# ESP32-S2_pacman.net
KiCad netlist of a schematic drawn in EAGLE
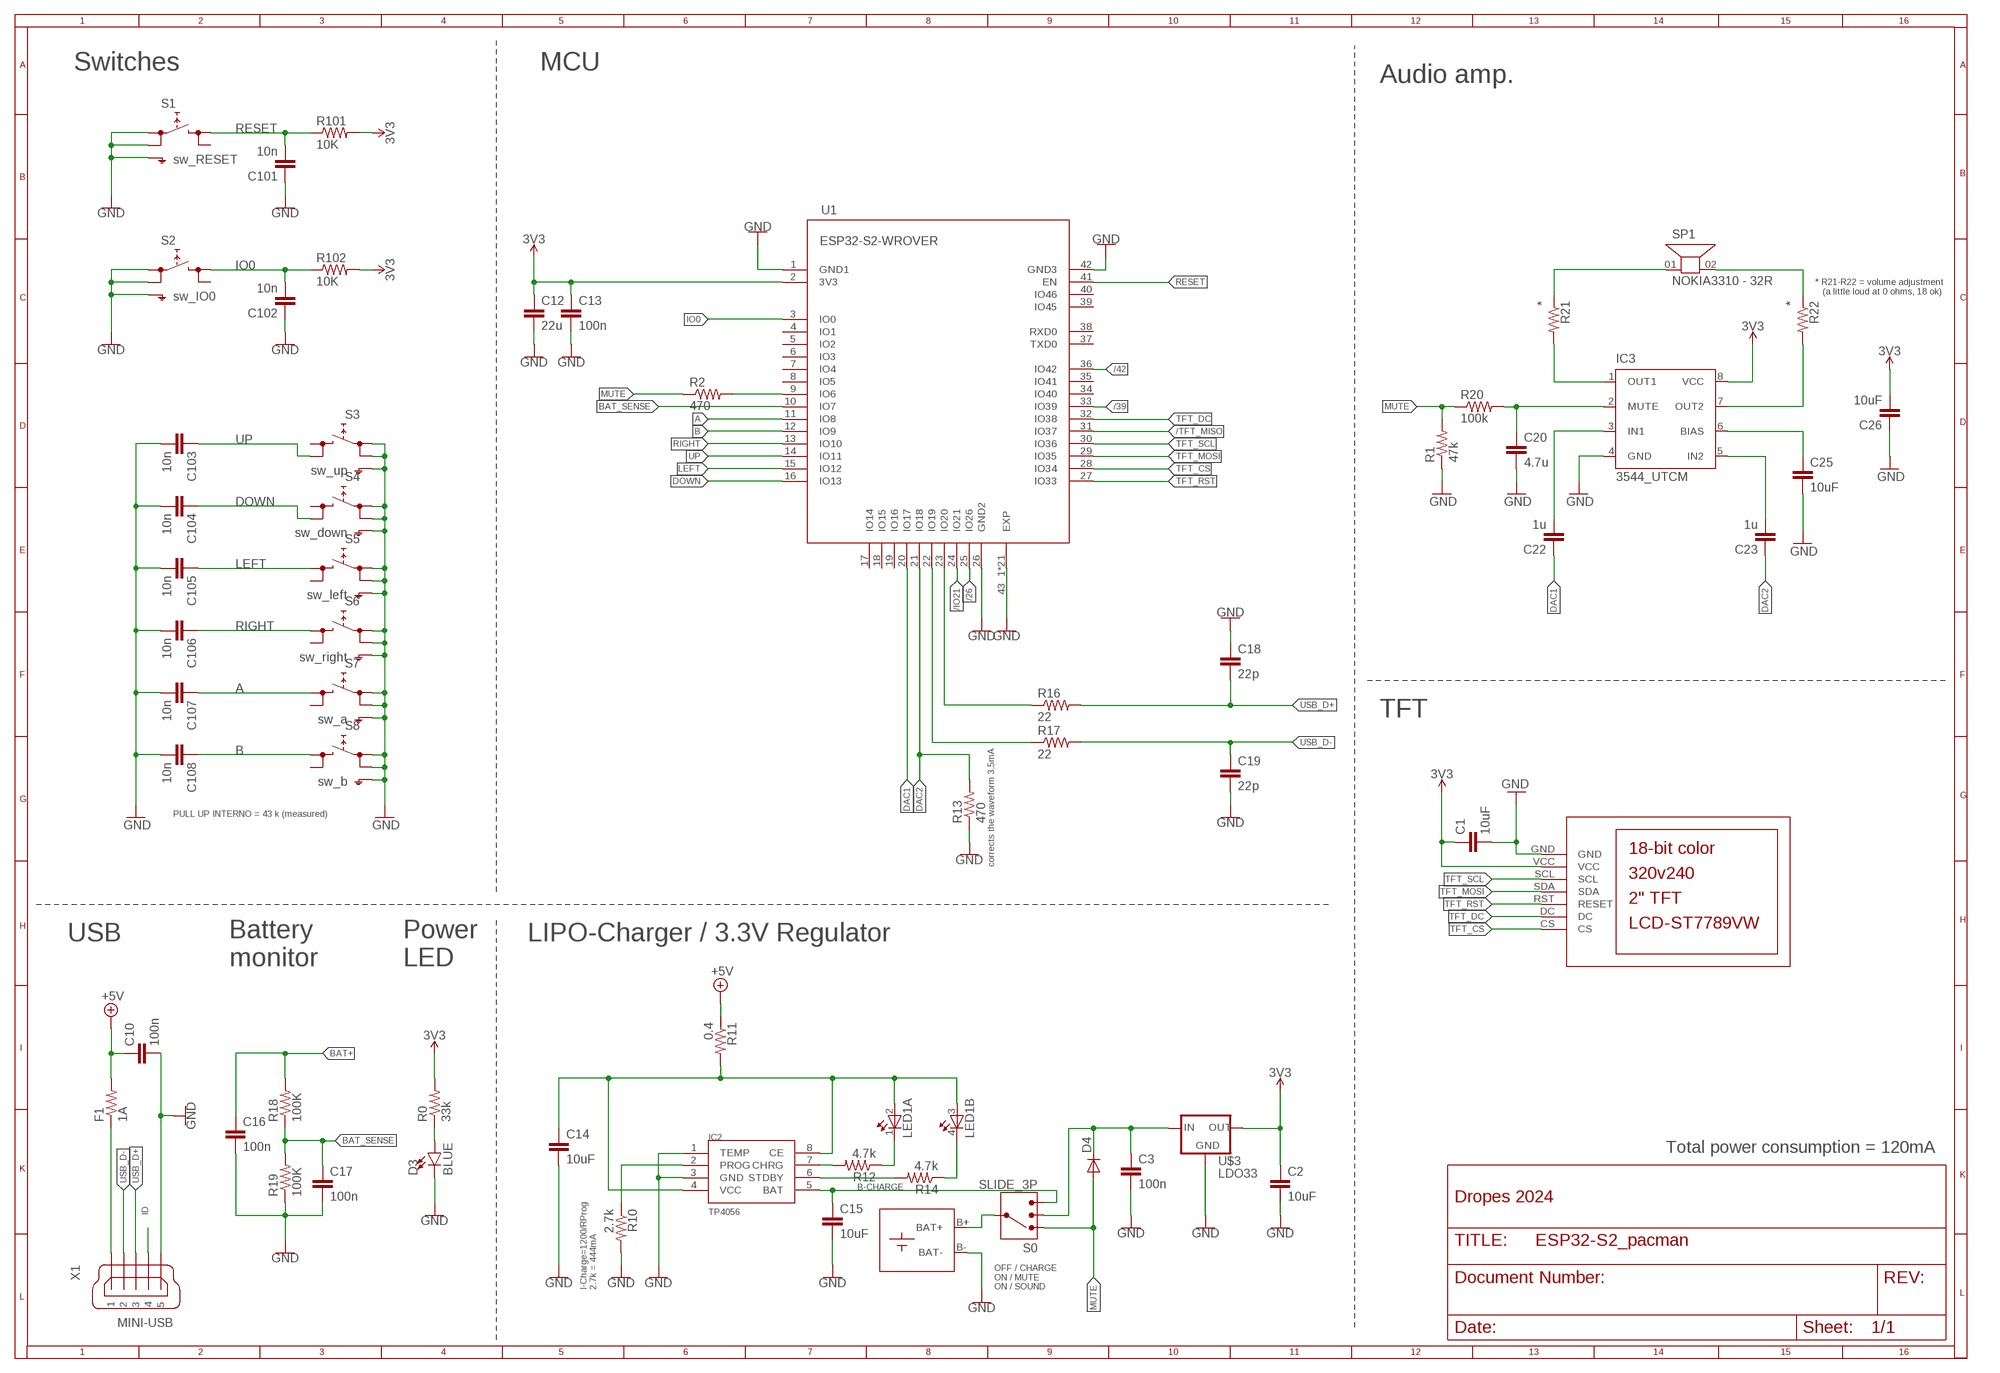
[diagram p0: schematic, sheet 1]

(export (version "E")
  (design (tool "Eeschema 10.0.6"))
  (components
    (comp (ref "C1")
      (value "10uF")
      (footprint "eagle-import:1206")
      (libsource (lib "eagle-import") (part "CAP1206"))
    )
    (comp (ref "C2")
      (value "10uF")
      (footprint "eagle-import:1206")
      (libsource (lib "eagle-import") (part "CAP1206"))
    )
    (comp (ref "C3")
      (value "100n")
      (footprint "eagle-import:0805")
      (libsource (lib "eagle-import") (part "CAP0805"))
    )
    (comp (ref "C10")
      (value "100n")
      (footprint "eagle-import:0805")
      (libsource (lib "eagle-import") (part "CAP0805"))
    )
    (comp (ref "C12")
      (value "22u")
      (footprint "eagle-import:1206")
      (libsource (lib "eagle-import") (part "CAP1206"))
    )
    (comp (ref "C13")
      (value "100n")
      (footprint "eagle-import:0805")
      (libsource (lib "eagle-import") (part "CAP0805"))
    )
    (comp (ref "C14")
      (value "10uF")
      (footprint "eagle-import:1206")
      (libsource (lib "eagle-import") (part "CAP1206"))
    )
    (comp (ref "C15")
      (value "10uF")
      (footprint "eagle-import:1206")
      (libsource (lib "eagle-import") (part "CAP1206"))
    )
    (comp (ref "C16")
      (value "100n")
      (footprint "eagle-import:0805")
      (libsource (lib "eagle-import") (part "CAP0805"))
    )
    (comp (ref "C17")
      (value "100n")
      (footprint "eagle-import:0805")
      (libsource (lib "eagle-import") (part "CAP0805"))
    )
    (comp (ref "C18")
      (value "22p")
      (footprint "eagle-import:0805")
      (libsource (lib "eagle-import") (part "CAP0805"))
    )
    (comp (ref "C19")
      (value "22p")
      (footprint "eagle-import:0805")
      (libsource (lib "eagle-import") (part "CAP0805"))
    )
    (comp (ref "C20")
      (value "4.7u")
      (footprint "eagle-import:0805")
      (libsource (lib "eagle-import") (part "CAP0805"))
    )
    (comp (ref "C22")
      (value "1u")
      (footprint "eagle-import:0805")
      (libsource (lib "eagle-import") (part "CAP0805"))
    )
    (comp (ref "C23")
      (value "1u")
      (footprint "eagle-import:0805")
      (libsource (lib "eagle-import") (part "CAP0805"))
    )
    (comp (ref "C25")
      (value "10uF")
      (footprint "eagle-import:0805")
      (libsource (lib "eagle-import") (part "CAP0805"))
    )
    (comp (ref "C26")
      (value "10uF")
      (footprint "eagle-import:0805")
      (libsource (lib "eagle-import") (part "CAP0805"))
    )
    (comp (ref "C101")
      (value "10n")
      (footprint "eagle-import:0805")
      (libsource (lib "eagle-import") (part "CAP0805"))
    )
    (comp (ref "C102")
      (value "10n")
      (footprint "eagle-import:0805")
      (libsource (lib "eagle-import") (part "CAP0805"))
    )
    (comp (ref "C103")
      (value "10n")
      (footprint "eagle-import:0805")
      (libsource (lib "eagle-import") (part "CAP0805"))
    )
    (comp (ref "C104")
      (value "10n")
      (footprint "eagle-import:0805")
      (libsource (lib "eagle-import") (part "CAP0805"))
    )
    (comp (ref "C105")
      (value "10n")
      (footprint "eagle-import:0805")
      (libsource (lib "eagle-import") (part "CAP0805"))
    )
    (comp (ref "C106")
      (value "10n")
      (footprint "eagle-import:0805")
      (libsource (lib "eagle-import") (part "CAP0805"))
    )
    (comp (ref "C107")
      (value "10n")
      (footprint "eagle-import:0805")
      (libsource (lib "eagle-import") (part "CAP0805"))
    )
    (comp (ref "C108")
      (value "10n")
      (footprint "eagle-import:0805")
      (libsource (lib "eagle-import") (part "CAP0805"))
    )
    (comp (ref "D3")
      (value "BLUE")
      (footprint "eagle-import:LED-1206")
      (libsource (lib "eagle-import") (part "LED-BLUE1206"))
    )
    (comp (ref "D4")
      (value "DIODE-SOD323-W")
      (footprint "eagle-import:SOD323-W")
      (libsource (lib "eagle-import") (part "DIODE-SOD323-W"))
    )
    (comp (ref "F1")
      (value "1A")
      (footprint "eagle-import:0805")
      (libsource (lib "eagle-import") (part "RESISTOR0805-RES"))
    )
    (comp (ref "IC2")
      (value "TP4056")
      (footprint "eagle-import:SOP-8")
      (libsource (lib "eagle-import") (part "TP4056"))
    )
    (comp (ref "IC3")
      (value "3544_UTCM")
      (footprint "eagle-import:SO08")
      (libsource (lib "eagle-import") (part "3544_UTCM"))
    )
    (comp (ref "LED1")
      (value "TOPLED-2--")
      (footprint "eagle-import:P-LCC-4-2")
      (libsource (lib "eagle-import") (part "TOPLED-2--"))
    )
    (comp (ref "R0")
      (value "33k")
      (footprint "eagle-import:0805")
      (libsource (lib "eagle-import") (part "RESISTOR0805-RES"))
    )
    (comp (ref "R1")
      (value "47k")
      (footprint "eagle-import:0805")
      (libsource (lib "eagle-import") (part "RESISTOR0805-RES"))
    )
    (comp (ref "R2")
      (value "470")
      (footprint "eagle-import:0805")
      (libsource (lib "eagle-import") (part "RESISTOR0805-RES"))
    )
    (comp (ref "R10")
      (value "2.7k")
      (footprint "eagle-import:0805")
      (libsource (lib "eagle-import") (part "RESISTOR0805-RES"))
    )
    (comp (ref "R11")
      (value "0.4")
      (footprint "eagle-import:0805")
      (libsource (lib "eagle-import") (part "RESISTOR0805-RES"))
    )
    (comp (ref "R12")
      (value "4.7k")
      (footprint "eagle-import:0805")
      (libsource (lib "eagle-import") (part "RESISTOR0805-RES"))
    )
    (comp (ref "R13")
      (value "470")
      (footprint "eagle-import:0805")
      (libsource (lib "eagle-import") (part "RESISTOR0805-RES"))
    )
    (comp (ref "R14")
      (value "4.7k")
      (footprint "eagle-import:0805")
      (libsource (lib "eagle-import") (part "RESISTOR0805-RES"))
    )
    (comp (ref "R16")
      (value "22")
      (footprint "eagle-import:0805")
      (libsource (lib "eagle-import") (part "RESISTOR0805-RES"))
    )
    (comp (ref "R17")
      (value "22")
      (footprint "eagle-import:0805")
      (libsource (lib "eagle-import") (part "RESISTOR0805-RES"))
    )
    (comp (ref "R18")
      (value "100K")
      (footprint "eagle-import:0805")
      (libsource (lib "eagle-import") (part "RESISTOR0805-RES"))
    )
    (comp (ref "R19")
      (value "100K")
      (footprint "eagle-import:0805")
      (libsource (lib "eagle-import") (part "RESISTOR0805-RES"))
    )
    (comp (ref "R20")
      (value "100k")
      (footprint "eagle-import:0805")
      (libsource (lib "eagle-import") (part "RESISTOR0805-RES"))
    )
    (comp (ref "R21")
      (value "*")
      (footprint "eagle-import:0805")
      (libsource (lib "eagle-import") (part "RESISTOR0805-RES"))
    )
    (comp (ref "R22")
      (value "*")
      (footprint "eagle-import:0805")
      (libsource (lib "eagle-import") (part "RESISTOR0805-RES"))
    )
    (comp (ref "R101")
      (value "10K")
      (footprint "eagle-import:0805")
      (libsource (lib "eagle-import") (part "RESISTOR0805-RES"))
    )
    (comp (ref "R102")
      (value "10K")
      (footprint "eagle-import:0805")
      (libsource (lib "eagle-import") (part "RESISTOR0805-RES"))
    )
    (comp (ref "S0")
      (value "SLIDE_3P")
      (footprint "eagle-import:SLIDE_3P")
      (libsource (lib "eagle-import") (part "SLIDE_3P"))
    )
    (comp (ref "S1")
      (value "sw_RESET")
      (footprint "eagle-import:SKHMPXE010")
      (libsource (lib "eagle-import") (part "SKHMPE010S"))
    )
    (comp (ref "S2")
      (value "sw_IO0")
      (footprint "eagle-import:SKHMPXE010")
      (libsource (lib "eagle-import") (part "SKHMPE010S"))
    )
    (comp (ref "S3")
      (value "sw_up")
      (footprint "eagle-import:SKHMPXE010")
      (libsource (lib "eagle-import") (part "SKHMPE010S"))
    )
    (comp (ref "S4")
      (value "sw_down")
      (footprint "eagle-import:SKHMPXE010")
      (libsource (lib "eagle-import") (part "SKHMPE010S"))
    )
    (comp (ref "S5")
      (value "sw_left")
      (footprint "eagle-import:SKHMPXE010")
      (libsource (lib "eagle-import") (part "SKHMPE010S"))
    )
    (comp (ref "S6")
      (value "sw_right")
      (footprint "eagle-import:SKHMPXE010")
      (libsource (lib "eagle-import") (part "SKHMPE010S"))
    )
    (comp (ref "S7")
      (value "sw_a")
      (footprint "eagle-import:SKHMPXE010")
      (libsource (lib "eagle-import") (part "SKHMPE010S"))
    )
    (comp (ref "S8")
      (value "sw_b")
      (footprint "eagle-import:SKHMPXE010")
      (libsource (lib "eagle-import") (part "SKHMPE010S"))
    )
    (comp (ref "SP1")
      (value "NOKIA3310 - 32R")
      (footprint "eagle-import:AL201P")
      (libsource (lib "eagle-import") (part "AL201P"))
    )
    (comp (ref "U$1")
      (value "NOKIA_LIPO")
      (footprint "eagle-import:BATTERY")
      (libsource (lib "eagle-import") (part "NOKIA_LIPO"))
    )
    (comp (ref "U$2")
      (value "LCD-ST7789VW")
      (footprint "eagle-import:LCD-ST7789VW")
      (libsource (lib "eagle-import") (part "LCD-ST7789VW"))
    )
    (comp (ref "U$3")
      (value "LDO33")
      (footprint "eagle-import:SOT89R")
      (libsource (lib "eagle-import") (part "LDO33"))
    )
    (comp (ref "U1")
      (value "ESP32-S2-WROVER")
      (footprint "eagle-import:MODULE_ESP32-S2-WROVER")
      (fields (field (name "MF") "Espressif Systems"))
      (libsource (lib "eagle-import") (part "ESP32-S2-WROVER"))
    )
    (comp (ref "X1")
      (value "MINI-USB")
      (footprint "eagle-import:32005-301")
      (libsource (lib "eagle-import") (part "MINI-USB-32005-301"))
    )
  )
  (nets
    (net (code "1") (name "+5V") (class "Default")
      (node (ref "C10") (pin "1") (pinfunction "1_1") (pintype "passive"))
      (node (ref "F1") (pin "2") (pinfunction "2_2") (pintype "passive"))
      (node (ref "R11") (pin "1") (pinfunction "1_1") (pintype "passive"))
    )
    (net (code "2") (name "/B-CHARGE") (class "Default")
      (node (ref "C15") (pin "1") (pinfunction "1_1") (pintype "passive"))
      (node (ref "IC2") (pin "5") (pinfunction "BAT_5") (pintype "bidirectional"))
      (node (ref "S0") (pin "P$4") (pinfunction "4_P$4") (pintype "passive"))
    )
    (net (code "3") (name "/ID") (class "Default")
      (node (ref "X1") (pin "4") (pinfunction "4_4") (pintype "passive"))
    )
    (net (code "4") (name "3V3") (class "Default")
      (node (ref "C1") (pin "1") (pinfunction "1_1") (pintype "passive"))
      (node (ref "C12") (pin "1") (pinfunction "1_1") (pintype "passive"))
      (node (ref "C13") (pin "1") (pinfunction "1_1") (pintype "passive"))
      (node (ref "C2") (pin "1") (pinfunction "1_1") (pintype "passive"))
      (node (ref "C26") (pin "2") (pinfunction "2_2") (pintype "passive"))
      (node (ref "IC3") (pin "8") (pinfunction "VCC_8") (pintype "power_in"))
      (node (ref "R0") (pin "2") (pinfunction "2_2") (pintype "passive"))
      (node (ref "R101") (pin "2") (pinfunction "2_2") (pintype "passive"))
      (node (ref "R102") (pin "2") (pinfunction "2_2") (pintype "passive"))
      (node (ref "U$2") (pin "VCC") (pinfunction "VCC_VCC") (pintype "power_in"))
      (node (ref "U$3") (pin "3") (pinfunction "OUT_3") (pintype "passive"))
      (node (ref "U1") (pin "2") (pinfunction "3V3_2") (pintype "power_in"))
    )
    (net (code "5") (name "A") (class "Default")
      (node (ref "C107") (pin "1") (pinfunction "1_1") (pintype "passive"))
      (node (ref "S7") (pin "3") (pinfunction "2.1_3") (pintype "passive"))
      (node (ref "U1") (pin "11") (pinfunction "IO8_11") (pintype "bidirectional"))
    )
    (net (code "6") (name "B") (class "Default")
      (node (ref "C108") (pin "1") (pinfunction "1_1") (pintype "passive"))
      (node (ref "S8") (pin "3") (pinfunction "2.1_3") (pintype "passive"))
      (node (ref "U1") (pin "12") (pinfunction "IO9_12") (pintype "bidirectional"))
    )
    (net (code "7") (name "BAT+") (class "Default")
      (node (ref "C16") (pin "1") (pinfunction "1_1") (pintype "passive"))
      (node (ref "R18") (pin "2") (pinfunction "2_2") (pintype "passive"))
      (node (ref "S0") (pin "P$1") (pinfunction "1_P$1") (pintype "passive"))
      (node (ref "U$1") (pin "B+") (pinfunction "BAT+_B+") (pintype "power_in"))
    )
    (net (code "8") (name "BAT_SENSE") (class "Default")
      (node (ref "C17") (pin "1") (pinfunction "1_1") (pintype "passive"))
      (node (ref "R18") (pin "1") (pinfunction "1_1") (pintype "passive"))
      (node (ref "R19") (pin "2") (pinfunction "2_2") (pintype "passive"))
      (node (ref "U1") (pin "10") (pinfunction "IO7_10") (pintype "bidirectional"))
    )
    (net (code "9") (name "DAC1") (class "Default")
      (node (ref "C22") (pin "1") (pinfunction "1_1") (pintype "passive"))
      (node (ref "U1") (pin "20") (pinfunction "IO17_20") (pintype "bidirectional"))
    )
    (net (code "10") (name "DAC2") (class "Default")
      (node (ref "C23") (pin "1") (pinfunction "1_1") (pintype "passive"))
      (node (ref "R13") (pin "2") (pinfunction "2_2") (pintype "passive"))
      (node (ref "U1") (pin "21") (pinfunction "IO18_21") (pintype "bidirectional"))
    )
    (net (code "11") (name "DOWN") (class "Default")
      (node (ref "C104") (pin "1") (pinfunction "1_1") (pintype "passive"))
      (node (ref "S4") (pin "4") (pinfunction "2.2_4") (pintype "passive"))
      (node (ref "U1") (pin "16") (pinfunction "IO13_16") (pintype "bidirectional"))
    )
    (net (code "12") (name "GND") (class "Default")
      (node (ref "C1") (pin "2") (pinfunction "2_2") (pintype "passive"))
      (node (ref "C10") (pin "2") (pinfunction "2_2") (pintype "passive"))
      (node (ref "C101") (pin "1") (pinfunction "1_1") (pintype "passive"))
      (node (ref "C102") (pin "1") (pinfunction "1_1") (pintype "passive"))
      (node (ref "C103") (pin "2") (pinfunction "2_2") (pintype "passive"))
      (node (ref "C104") (pin "2") (pinfunction "2_2") (pintype "passive"))
      (node (ref "C105") (pin "2") (pinfunction "2_2") (pintype "passive"))
      (node (ref "C106") (pin "2") (pinfunction "2_2") (pintype "passive"))
      (node (ref "C107") (pin "2") (pinfunction "2_2") (pintype "passive"))
      (node (ref "C108") (pin "2") (pinfunction "2_2") (pintype "passive"))
      (node (ref "C12") (pin "2") (pinfunction "2_2") (pintype "passive"))
      (node (ref "C13") (pin "2") (pinfunction "2_2") (pintype "passive"))
      (node (ref "C14") (pin "2") (pinfunction "2_2") (pintype "passive"))
      (node (ref "C15") (pin "2") (pinfunction "2_2") (pintype "passive"))
      (node (ref "C16") (pin "2") (pinfunction "2_2") (pintype "passive"))
      (node (ref "C17") (pin "2") (pinfunction "2_2") (pintype "passive"))
      (node (ref "C18") (pin "1") (pinfunction "1_1") (pintype "passive"))
      (node (ref "C19") (pin "2") (pinfunction "2_2") (pintype "passive"))
      (node (ref "C2") (pin "2") (pinfunction "2_2") (pintype "passive"))
      (node (ref "C20") (pin "2") (pinfunction "2_2") (pintype "passive"))
      (node (ref "C25") (pin "2") (pinfunction "2_2") (pintype "passive"))
      (node (ref "C26") (pin "1") (pinfunction "1_1") (pintype "passive"))
      (node (ref "C3") (pin "2") (pinfunction "2_2") (pintype "passive"))
      (node (ref "D3") (pin "C") (pinfunction "C_C") (pintype "passive"))
      (node (ref "IC2") (pin "1") (pinfunction "TEMP_1") (pintype "bidirectional"))
      (node (ref "IC2") (pin "3") (pinfunction "GND_3") (pintype "bidirectional"))
      (node (ref "IC3") (pin "4") (pinfunction "GND_4") (pintype "power_in"))
      (node (ref "R1") (pin "1") (pinfunction "1_1") (pintype "passive"))
      (node (ref "R10") (pin "2") (pinfunction "2_2") (pintype "passive"))
      (node (ref "R13") (pin "1") (pinfunction "1_1") (pintype "passive"))
      (node (ref "R19") (pin "1") (pinfunction "1_1") (pintype "passive"))
      (node (ref "S1") (pin "1") (pinfunction "1.1_1") (pintype "passive"))
      (node (ref "S1") (pin "2") (pinfunction "1.2_2") (pintype "passive"))
      (node (ref "S1") (pin "5") (pinfunction "SH_5") (pintype "passive"))
      (node (ref "S2") (pin "1") (pinfunction "1.1_1") (pintype "passive"))
      (node (ref "S2") (pin "2") (pinfunction "1.2_2") (pintype "passive"))
      (node (ref "S2") (pin "5") (pinfunction "SH_5") (pintype "passive"))
      (node (ref "S3") (pin "1") (pinfunction "1.1_1") (pintype "passive"))
      (node (ref "S3") (pin "2") (pinfunction "1.2_2") (pintype "passive"))
      (node (ref "S3") (pin "5") (pinfunction "SH_5") (pintype "passive"))
      (node (ref "S4") (pin "1") (pinfunction "1.1_1") (pintype "passive"))
      (node (ref "S4") (pin "2") (pinfunction "1.2_2") (pintype "passive"))
      (node (ref "S4") (pin "5") (pinfunction "SH_5") (pintype "passive"))
      (node (ref "S5") (pin "1") (pinfunction "1.1_1") (pintype "passive"))
      (node (ref "S5") (pin "2") (pinfunction "1.2_2") (pintype "passive"))
      (node (ref "S5") (pin "5") (pinfunction "SH_5") (pintype "passive"))
      (node (ref "S6") (pin "1") (pinfunction "1.1_1") (pintype "passive"))
      (node (ref "S6") (pin "2") (pinfunction "1.2_2") (pintype "passive"))
      (node (ref "S6") (pin "5") (pinfunction "SH_5") (pintype "passive"))
      (node (ref "S7") (pin "1") (pinfunction "1.1_1") (pintype "passive"))
      (node (ref "S7") (pin "2") (pinfunction "1.2_2") (pintype "passive"))
      (node (ref "S7") (pin "5") (pinfunction "SH_5") (pintype "passive"))
      (node (ref "S8") (pin "1") (pinfunction "1.1_1") (pintype "passive"))
      (node (ref "S8") (pin "2") (pinfunction "1.2_2") (pintype "passive"))
      (node (ref "S8") (pin "5") (pinfunction "SH_5") (pintype "passive"))
      (node (ref "U$1") (pin "B-") (pinfunction "BAT-_B-") (pintype "power_in"))
      (node (ref "U$2") (pin "GND") (pinfunction "GND_GND") (pintype "power_in"))
      (node (ref "U$3") (pin "1") (pinfunction "GND_1") (pintype "input"))
      (node (ref "U1") (pin "1") (pinfunction "GND1_1") (pintype "power_in"))
      (node (ref "U1") (pin "26") (pinfunction "GND2_26") (pintype "power_in"))
      (node (ref "U1") (pin "42") (pinfunction "GND3_42") (pintype "power_in"))
      (node (ref "U1") (pin "43_1") (pinfunction "EXP_43_1") (pintype "power_in"))
      (node (ref "U1") (pin "43_10") (pinfunction "EXP_43_10") (pintype "power_in"))
      (node (ref "U1") (pin "43_11") (pinfunction "EXP_43_11") (pintype "power_in"))
      (node (ref "U1") (pin "43_12") (pinfunction "EXP_43_12") (pintype "power_in"))
      (node (ref "U1") (pin "43_13") (pinfunction "EXP_43_13") (pintype "power_in"))
      (node (ref "U1") (pin "43_14") (pinfunction "EXP_43_14") (pintype "power_in"))
      (node (ref "U1") (pin "43_15") (pinfunction "EXP_43_15") (pintype "power_in"))
      (node (ref "U1") (pin "43_16") (pinfunction "EXP_43_16") (pintype "power_in"))
      (node (ref "U1") (pin "43_17") (pinfunction "EXP_43_17") (pintype "power_in"))
      (node (ref "U1") (pin "43_18") (pinfunction "EXP_43_18") (pintype "power_in"))
      (node (ref "U1") (pin "43_19") (pinfunction "EXP_43_19") (pintype "power_in"))
      (node (ref "U1") (pin "43_2") (pinfunction "EXP_43_2") (pintype "power_in"))
      (node (ref "U1") (pin "43_20") (pinfunction "EXP_43_20") (pintype "power_in"))
      (node (ref "U1") (pin "43_21") (pinfunction "EXP_43_21") (pintype "power_in"))
      (node (ref "U1") (pin "43_3") (pinfunction "EXP_43_3") (pintype "power_in"))
      (node (ref "U1") (pin "43_4") (pinfunction "EXP_43_4") (pintype "power_in"))
      (node (ref "U1") (pin "43_5") (pinfunction "EXP_43_5") (pintype "power_in"))
      (node (ref "U1") (pin "43_6") (pinfunction "EXP_43_6") (pintype "power_in"))
      (node (ref "U1") (pin "43_7") (pinfunction "EXP_43_7") (pintype "power_in"))
      (node (ref "U1") (pin "43_8") (pinfunction "EXP_43_8") (pintype "power_in"))
      (node (ref "U1") (pin "43_9") (pinfunction "EXP_43_9") (pintype "power_in"))
      (node (ref "X1") (pin "5") (pinfunction "5_5") (pintype "passive"))
    )
    (net (code "13") (name "IO0") (class "Default")
      (node (ref "C102") (pin "2") (pinfunction "2_2") (pintype "passive"))
      (node (ref "R102") (pin "1") (pinfunction "1_1") (pintype "passive"))
      (node (ref "S2") (pin "3") (pinfunction "2.1_3") (pintype "passive"))
      (node (ref "U1") (pin "3") (pinfunction "IO0_3") (pintype "bidirectional"))
    )
    (net (code "14") (name "LEFT") (class "Default")
      (node (ref "C105") (pin "1") (pinfunction "1_1") (pintype "passive"))
      (node (ref "S5") (pin "3") (pinfunction "2.1_3") (pintype "passive"))
      (node (ref "U1") (pin "15") (pinfunction "IO12_15") (pintype "bidirectional"))
    )
    (net (code "15") (name "MUTE") (class "Default")
      (node (ref "D4") (pin "A") (pinfunction "A_A") (pintype "passive"))
      (node (ref "R1") (pin "2") (pinfunction "2_2") (pintype "passive"))
      (node (ref "R2") (pin "1") (pinfunction "1_1") (pintype "passive"))
      (node (ref "R20") (pin "1") (pinfunction "1_1") (pintype "passive"))
      (node (ref "S0") (pin "P$2") (pinfunction "2_P$2") (pintype "passive"))
    )
    (net (code "16") (name "Net-(D3-PadA)") (class "Default")
      (node (ref "D3") (pin "A") (pinfunction "A_A") (pintype "passive"))
      (node (ref "R0") (pin "1") (pinfunction "1_1") (pintype "passive"))
    )
    (net (code "17") (name "Net-(F1-Pad1)") (class "Default")
      (node (ref "F1") (pin "1") (pinfunction "1_1") (pintype "passive"))
      (node (ref "X1") (pin "1") (pinfunction "1_1") (pintype "passive"))
    )
    (net (code "18") (name "Net-(IC2-CE)") (class "Default")
      (node (ref "C14") (pin "1") (pinfunction "1_1") (pintype "passive"))
      (node (ref "IC2") (pin "4") (pinfunction "VCC_4") (pintype "bidirectional"))
      (node (ref "IC2") (pin "8") (pinfunction "CE_8") (pintype "bidirectional"))
      (node (ref "LED1") (pin "2") (pinfunction "A_2") (pintype "passive"))
      (node (ref "LED1") (pin "3") (pinfunction "A_3") (pintype "passive"))
      (node (ref "R11") (pin "2") (pinfunction "2_2") (pintype "passive"))
    )
    (net (code "19") (name "Net-(IC2-CHRG)") (class "Default")
      (node (ref "IC2") (pin "7") (pinfunction "CHRG_7") (pintype "bidirectional"))
      (node (ref "R12") (pin "2") (pinfunction "2_2") (pintype "passive"))
    )
    (net (code "20") (name "Net-(IC2-PROG)") (class "Default")
      (node (ref "IC2") (pin "2") (pinfunction "PROG_2") (pintype "bidirectional"))
      (node (ref "R10") (pin "1") (pinfunction "1_1") (pintype "passive"))
    )
    (net (code "21") (name "Net-(IC2-STDBY)") (class "Default")
      (node (ref "IC2") (pin "6") (pinfunction "STDBY_6") (pintype "bidirectional"))
      (node (ref "R14") (pin "2") (pinfunction "2_2") (pintype "passive"))
    )
    (net (code "22") (name "Net-(IC3-BIAS)") (class "Default")
      (node (ref "C25") (pin "1") (pinfunction "1_1") (pintype "passive"))
      (node (ref "IC3") (pin "6") (pinfunction "BIAS_6") (pintype "input"))
    )
    (net (code "23") (name "Net-(IC3-IN1)") (class "Default")
      (node (ref "C22") (pin "2") (pinfunction "2_2") (pintype "passive"))
      (node (ref "IC3") (pin "3") (pinfunction "IN1_3") (pintype "input"))
    )
    (net (code "24") (name "Net-(IC3-IN2)") (class "Default")
      (node (ref "C23") (pin "2") (pinfunction "2_2") (pintype "passive"))
      (node (ref "IC3") (pin "5") (pinfunction "IN2_5") (pintype "input"))
    )
    (net (code "25") (name "Net-(IC3-MUTE)") (class "Default")
      (node (ref "C20") (pin "1") (pinfunction "1_1") (pintype "passive"))
      (node (ref "IC3") (pin "2") (pinfunction "MUTE_2") (pintype "input"))
      (node (ref "R20") (pin "2") (pinfunction "2_2") (pintype "passive"))
    )
    (net (code "26") (name "Net-(IC3-OUT1)") (class "Default")
      (node (ref "IC3") (pin "1") (pinfunction "OUT1_1") (pintype "output"))
      (node (ref "R21") (pin "2") (pinfunction "2_2") (pintype "passive"))
    )
    (net (code "27") (name "Net-(IC3-OUT2)") (class "Default")
      (node (ref "IC3") (pin "7") (pinfunction "OUT2_7") (pintype "output"))
      (node (ref "R22") (pin "2") (pinfunction "2_2") (pintype "passive"))
    )
    (net (code "28") (name "Net-(LED1A-C)") (class "Default")
      (node (ref "LED1") (pin "1") (pinfunction "C_1") (pintype "passive"))
      (node (ref "R12") (pin "1") (pinfunction "1_1") (pintype "passive"))
    )
    (net (code "29") (name "Net-(LED1B-C)") (class "Default")
      (node (ref "LED1") (pin "4") (pinfunction "C_4") (pintype "passive"))
      (node (ref "R14") (pin "1") (pinfunction "1_1") (pintype "passive"))
    )
    (net (code "30") (name "Net-(S0-3)") (class "Default")
      (node (ref "C3") (pin "1") (pinfunction "1_1") (pintype "passive"))
      (node (ref "D4") (pin "C") (pinfunction "C_C") (pintype "passive"))
      (node (ref "S0") (pin "P$3") (pinfunction "3_P$3") (pintype "passive"))
      (node (ref "U$3") (pin "'2") (pinfunction "IN_'2") (pintype "input"))
      (node (ref "U$3") (pin "2") (pinfunction "IN_2") (pintype "input"))
    )
    (net (code "31") (name "Net-(SP1-1)") (class "Default")
      (node (ref "R21") (pin "1") (pinfunction "1_1") (pintype "passive"))
      (node (ref "SP1") (pin "01") (pinfunction "1_01") (pintype "passive"))
    )
    (net (code "32") (name "Net-(SP1-2)") (class "Default")
      (node (ref "R22") (pin "1") (pinfunction "1_1") (pintype "passive"))
      (node (ref "SP1") (pin "02") (pinfunction "2_02") (pintype "passive"))
    )
    (net (code "33") (name "Net-(U1-IO6)") (class "Default")
      (node (ref "R2") (pin "2") (pinfunction "2_2") (pintype "passive"))
      (node (ref "U1") (pin "9") (pinfunction "IO6_9") (pintype "bidirectional"))
    )
    (net (code "34") (name "Net-(U1-IO19)") (class "Default")
      (node (ref "R17") (pin "1") (pinfunction "1_1") (pintype "passive"))
      (node (ref "U1") (pin "22") (pinfunction "IO19_22") (pintype "bidirectional"))
    )
    (net (code "35") (name "Net-(U1-IO20)") (class "Default")
      (node (ref "R16") (pin "1") (pinfunction "1_1") (pintype "passive"))
      (node (ref "U1") (pin "23") (pinfunction "IO20_23") (pintype "bidirectional"))
    )
    (net (code "36") (name "RESET") (class "Default")
      (node (ref "C101") (pin "2") (pinfunction "2_2") (pintype "passive"))
      (node (ref "R101") (pin "1") (pinfunction "1_1") (pintype "passive"))
      (node (ref "S1") (pin "3") (pinfunction "2.1_3") (pintype "passive"))
      (node (ref "U1") (pin "41") (pinfunction "EN_41") (pintype "input"))
    )
    (net (code "37") (name "RIGHT") (class "Default")
      (node (ref "C106") (pin "1") (pinfunction "1_1") (pintype "passive"))
      (node (ref "S6") (pin "3") (pinfunction "2.1_3") (pintype "passive"))
      (node (ref "U1") (pin "13") (pinfunction "IO10_13") (pintype "bidirectional"))
    )
    (net (code "38") (name "TFT_CS") (class "Default")
      (node (ref "U$2") (pin "CS") (pinfunction "CS_CS") (pintype "input"))
      (node (ref "U1") (pin "28") (pinfunction "IO34_28") (pintype "input"))
    )
    (net (code "39") (name "TFT_DC") (class "Default")
      (node (ref "U$2") (pin "DC") (pinfunction "DC_DC") (pintype "input"))
      (node (ref "U1") (pin "32") (pinfunction "IO38_32") (pintype "bidirectional"))
    )
    (net (code "40") (name "TFT_MOSI") (class "Default")
      (node (ref "U$2") (pin "SDA") (pinfunction "SDA_SDA") (pintype "bidirectional"))
      (node (ref "U1") (pin "29") (pinfunction "IO35_29") (pintype "input"))
    )
    (net (code "41") (name "TFT_RST") (class "Default")
      (node (ref "U$2") (pin "RST") (pinfunction "RESET_RST") (pintype "input"))
      (node (ref "U1") (pin "27") (pinfunction "IO33_27") (pintype "bidirectional"))
    )
    (net (code "42") (name "TFT_SCL") (class "Default")
      (node (ref "U$2") (pin "SCL") (pinfunction "SCL_SCL") (pintype "input"))
      (node (ref "U1") (pin "30") (pinfunction "IO36_30") (pintype "bidirectional"))
    )
    (net (code "43") (name "UP") (class "Default")
      (node (ref "C103") (pin "1") (pinfunction "1_1") (pintype "passive"))
      (node (ref "S3") (pin "4") (pinfunction "2.2_4") (pintype "passive"))
      (node (ref "U1") (pin "14") (pinfunction "IO11_14") (pintype "bidirectional"))
    )
    (net (code "44") (name "USB_D+") (class "Default")
      (node (ref "C18") (pin "2") (pinfunction "2_2") (pintype "passive"))
      (node (ref "R16") (pin "2") (pinfunction "2_2") (pintype "passive"))
      (node (ref "X1") (pin "3") (pinfunction "3_3") (pintype "passive"))
    )
    (net (code "45") (name "USB_D-") (class "Default")
      (node (ref "C19") (pin "1") (pinfunction "1_1") (pintype "passive"))
      (node (ref "R17") (pin "2") (pinfunction "2_2") (pintype "passive"))
      (node (ref "X1") (pin "2") (pinfunction "2_2") (pintype "passive"))
    )
    (net (code "46") (name "unconnected-(S1-2.2-Pad4)") (class "Default")
      (node (ref "S1") (pin "4") (pinfunction "2.2_4") (pintype "passive"))
    )
    (net (code "47") (name "unconnected-(S2-2.2-Pad4)") (class "Default")
      (node (ref "S2") (pin "4") (pinfunction "2.2_4") (pintype "passive"))
    )
    (net (code "48") (name "unconnected-(S3-2.1-Pad3)") (class "Default")
      (node (ref "S3") (pin "3") (pinfunction "2.1_3") (pintype "passive"))
    )
    (net (code "49") (name "unconnected-(S4-2.1-Pad3)") (class "Default")
      (node (ref "S4") (pin "3") (pinfunction "2.1_3") (pintype "passive"))
    )
    (net (code "50") (name "unconnected-(S5-2.2-Pad4)") (class "Default")
      (node (ref "S5") (pin "4") (pinfunction "2.2_4") (pintype "passive"))
    )
    (net (code "51") (name "unconnected-(S6-2.2-Pad4)") (class "Default")
      (node (ref "S6") (pin "4") (pinfunction "2.2_4") (pintype "passive"))
    )
    (net (code "52") (name "unconnected-(S7-2.2-Pad4)") (class "Default")
      (node (ref "S7") (pin "4") (pinfunction "2.2_4") (pintype "passive"))
    )
    (net (code "53") (name "unconnected-(S8-2.2-Pad4)") (class "Default")
      (node (ref "S8") (pin "4") (pinfunction "2.2_4") (pintype "passive"))
    )
    (net (code "54") (name "unconnected-(U1-IO1-Pad4)") (class "Default")
      (node (ref "U1") (pin "4") (pinfunction "IO1_4") (pintype "bidirectional"))
    )
    (net (code "55") (name "unconnected-(U1-IO2-Pad5)") (class "Default")
      (node (ref "U1") (pin "5") (pinfunction "IO2_5") (pintype "bidirectional"))
    )
    (net (code "56") (name "unconnected-(U1-IO3-Pad6)") (class "Default")
      (node (ref "U1") (pin "6") (pinfunction "IO3_6") (pintype "bidirectional"))
    )
    (net (code "57") (name "unconnected-(U1-IO4-Pad7)") (class "Default")
      (node (ref "U1") (pin "7") (pinfunction "IO4_7") (pintype "bidirectional"))
    )
    (net (code "58") (name "unconnected-(U1-IO5-Pad8)") (class "Default")
      (node (ref "U1") (pin "8") (pinfunction "IO5_8") (pintype "bidirectional"))
    )
    (net (code "59") (name "unconnected-(U1-IO14-Pad17)") (class "Default")
      (node (ref "U1") (pin "17") (pinfunction "IO14_17") (pintype "bidirectional"))
    )
    (net (code "60") (name "unconnected-(U1-IO15-Pad18)") (class "Default")
      (node (ref "U1") (pin "18") (pinfunction "IO15_18") (pintype "bidirectional"))
    )
    (net (code "61") (name "unconnected-(U1-IO16-Pad19)") (class "Default")
      (node (ref "U1") (pin "19") (pinfunction "IO16_19") (pintype "bidirectional"))
    )
    (net (code "62") (name "unconnected-(U1-IO40-Pad34)") (class "Default")
      (node (ref "U1") (pin "34") (pinfunction "IO40_34") (pintype "bidirectional"))
    )
    (net (code "63") (name "unconnected-(U1-IO41-Pad35)") (class "Default")
      (node (ref "U1") (pin "35") (pinfunction "IO41_35") (pintype "bidirectional"))
    )
    (net (code "64") (name "unconnected-(U1-IO45-Pad39)") (class "Default")
      (node (ref "U1") (pin "39") (pinfunction "IO45_39") (pintype "bidirectional"))
    )
    (net (code "65") (name "unconnected-(U1-IO46-Pad40)") (class "Default")
      (node (ref "U1") (pin "40") (pinfunction "IO46_40") (pintype "input"))
    )
    (net (code "66") (name "unconnected-(U1-RXD0-Pad38)") (class "Default")
      (node (ref "U1") (pin "38") (pinfunction "RXD0_38") (pintype "bidirectional"))
    )
    (net (code "67") (name "unconnected-(U1-TXD0-Pad37)") (class "Default")
      (node (ref "U1") (pin "37") (pinfunction "TXD0_37") (pintype "bidirectional"))
    )
    (net (code "68") (name "{slash}26") (class "Default")
      (node (ref "U1") (pin "25") (pinfunction "IO26_25") (pintype "bidirectional"))
    )
    (net (code "69") (name "{slash}39") (class "Default")
      (node (ref "U1") (pin "33") (pinfunction "IO39_33") (pintype "bidirectional"))
    )
    (net (code "70") (name "{slash}42") (class "Default")
      (node (ref "U1") (pin "36") (pinfunction "IO42_36") (pintype "bidirectional"))
    )
    (net (code "71") (name "{slash}IO21") (class "Default")
      (node (ref "U1") (pin "24") (pinfunction "IO21_24") (pintype "bidirectional"))
    )
    (net (code "72") (name "{slash}TFT_MISO") (class "Default")
      (node (ref "U1") (pin "31") (pinfunction "IO37_31") (pintype "bidirectional"))
    )
  )
)
